# MCU.net
KiCad netlist of a schematic drawn in Altium Designer
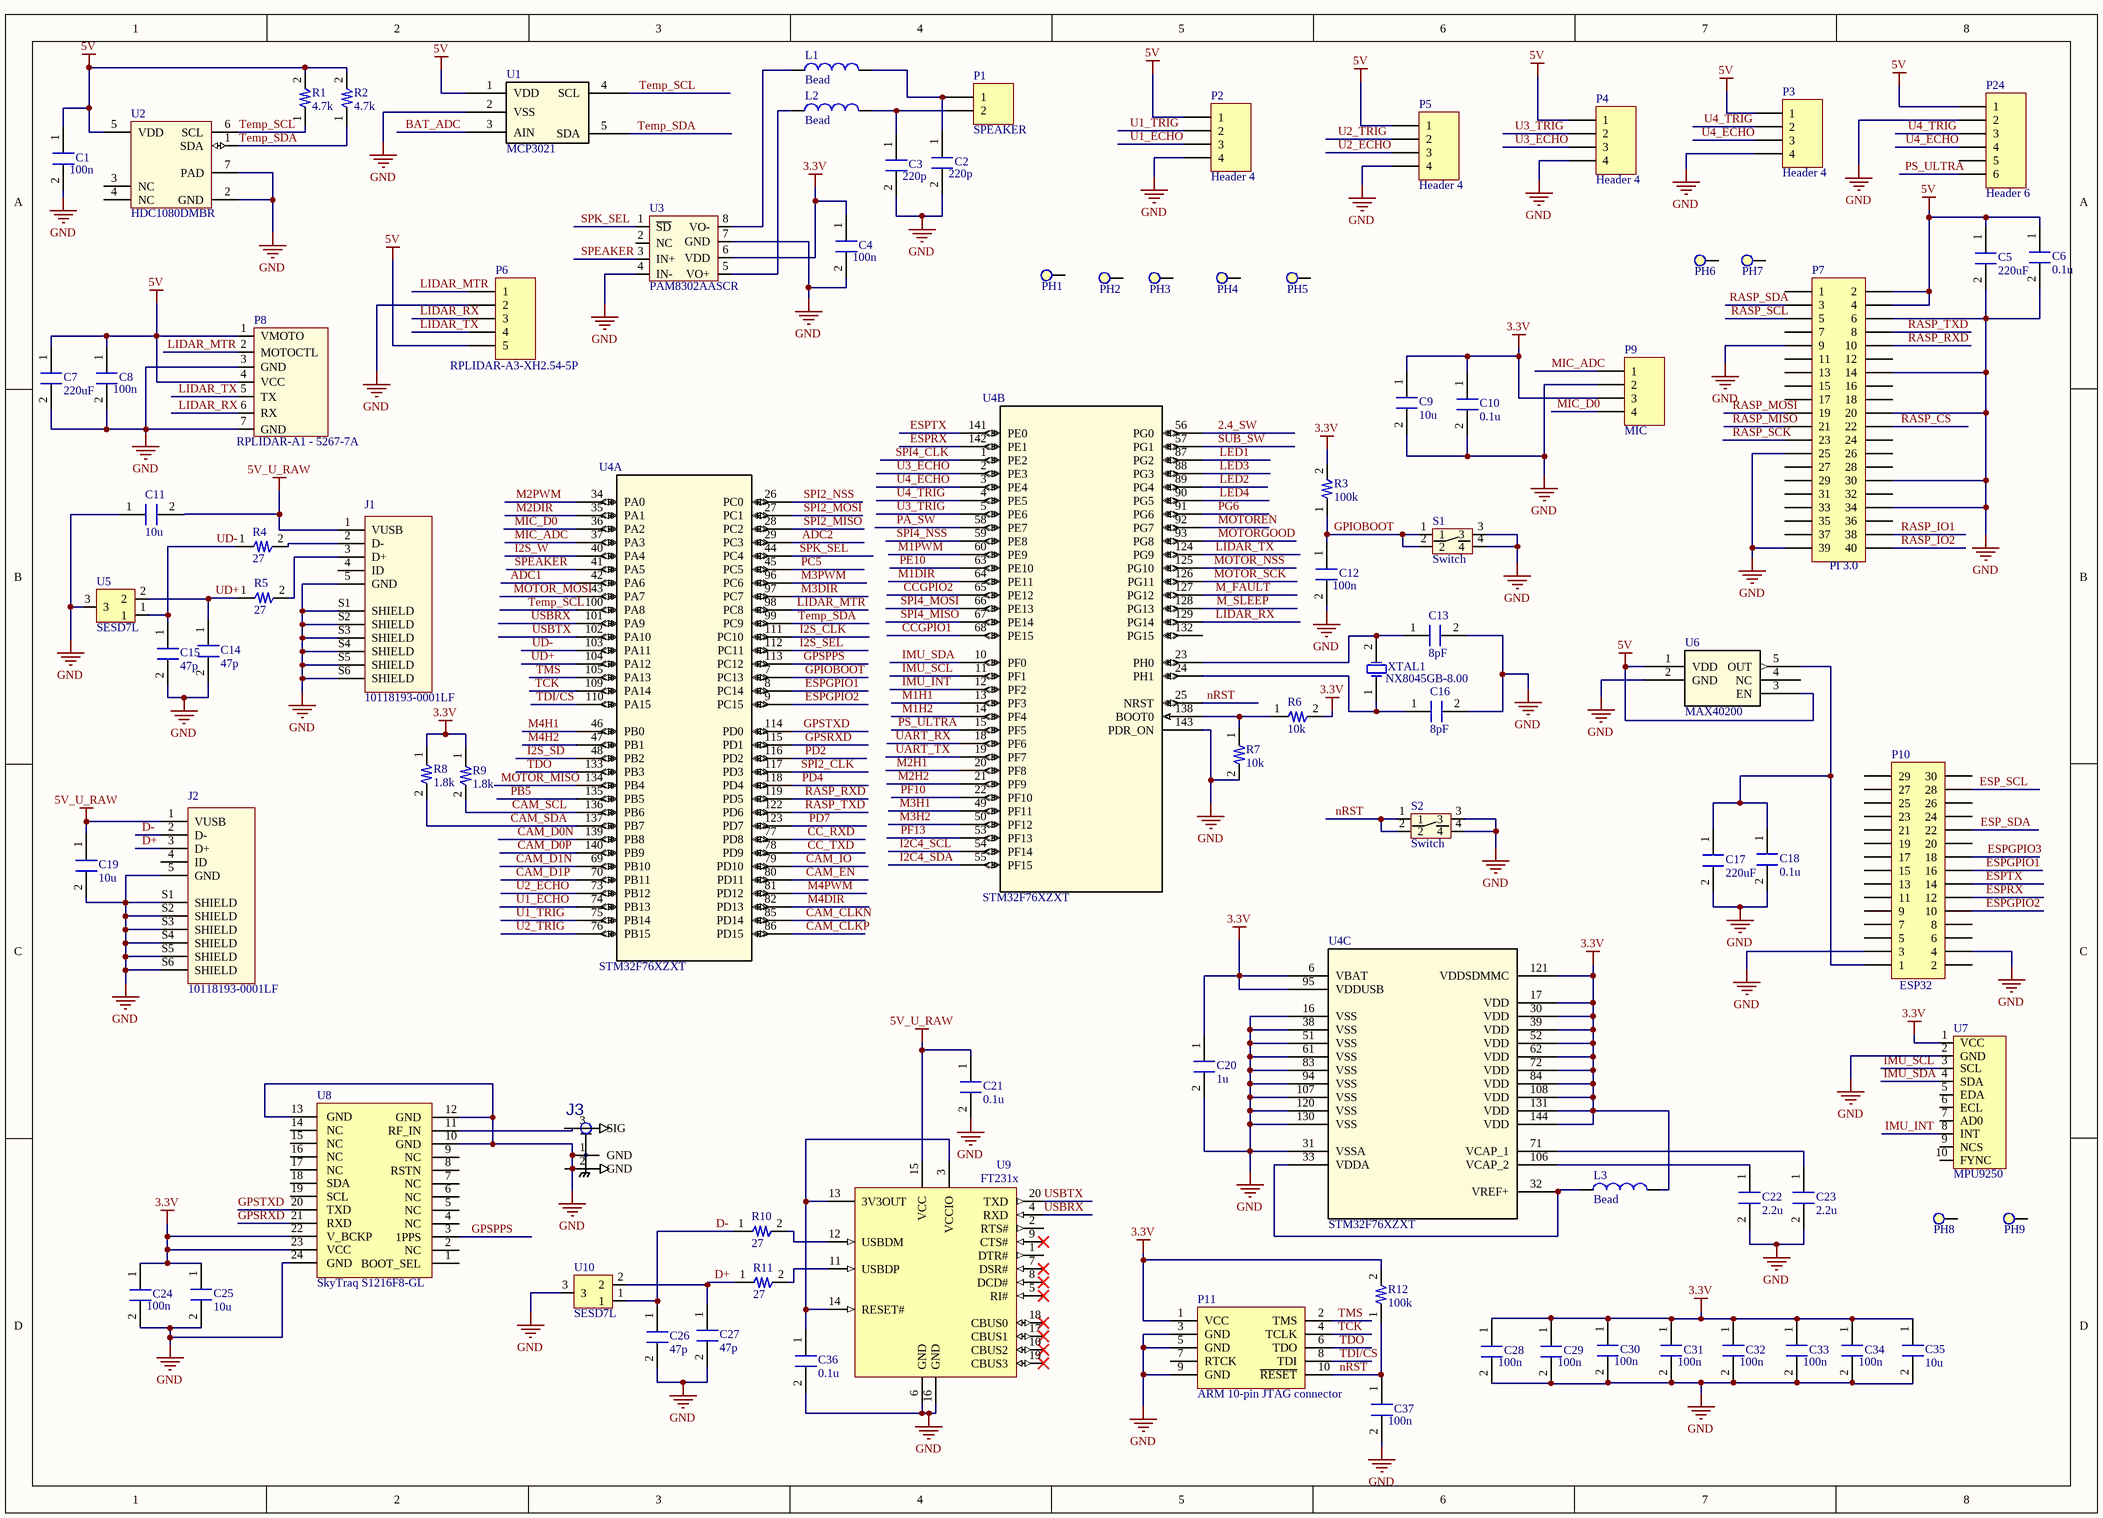
[diagram p0: MCU.SchDoc]

(export (version "E")
  (design (tool "Eeschema 10.0.6"))
  (components
    (comp (ref "C1")
      (value "100n")
      (footprint "Capacitor 0402")
      (fields (field (name "Comment") "Ceramic Capacitor"))
      (libsource (lib "Custom") (part "Ceramic Capacitor"))
    )
    (comp (ref "C2")
      (value "220p")
      (footprint "Capacitor 0402")
      (fields (field (name "Comment") "Ceramic Capacitor"))
      (libsource (lib "Custom") (part "Ceramic Capacitor"))
    )
    (comp (ref "C3")
      (value "220p")
      (footprint "Capacitor 0402")
      (fields (field (name "Comment") "Ceramic Capacitor"))
      (libsource (lib "Custom") (part "Ceramic Capacitor"))
    )
    (comp (ref "C4")
      (value "100n")
      (footprint "Capacitor 0402")
      (fields (field (name "Comment") "Ceramic Capacitor"))
      (libsource (lib "Custom") (part "Ceramic Capacitor"))
    )
    (comp (ref "C5")
      (value "220uF")
      (footprint "CAPAE250P680X1220_VERT")
      (fields (field (name "Comment") "Ceramic Capacitor"))
      (libsource (lib "Custom") (part "Ceramic Capacitor"))
    )
    (comp (ref "C6")
      (value "0.1u")
      (footprint "Capacitor 0402")
      (fields (field (name "Comment") "Ceramic Capacitor"))
      (libsource (lib "Custom") (part "Ceramic Capacitor"))
    )
    (comp (ref "C7")
      (value "220uF")
      (footprint "CAPAE250P680X1220_VERT")
      (fields (field (name "Comment") "Ceramic Capacitor"))
      (libsource (lib "Custom") (part "Ceramic Capacitor"))
    )
    (comp (ref "C8")
      (value "100n")
      (footprint "Capacitor 0402")
      (fields (field (name "Comment") "Ceramic Capacitor"))
      (libsource (lib "Custom") (part "Ceramic Capacitor"))
    )
    (comp (ref "C9")
      (value "10u")
      (footprint "Capacitor 0603")
      (fields (field (name "Comment") "Ceramic Capacitor"))
      (libsource (lib "Custom") (part "Ceramic Capacitor"))
    )
    (comp (ref "C10")
      (value "0.1u")
      (footprint "Capacitor 0402")
      (fields (field (name "Comment") "Ceramic Capacitor"))
      (libsource (lib "Custom") (part "Ceramic Capacitor"))
    )
    (comp (ref "C11")
      (value "10u")
      (footprint "Capacitor 0603")
      (fields (field (name "Comment") "Ceramic Capacitor"))
      (libsource (lib "Custom") (part "Ceramic Capacitor"))
    )
    (comp (ref "C12")
      (value "100n")
      (footprint "Capacitor 0402")
      (fields (field (name "Comment") "Ceramic Capacitor"))
      (libsource (lib "Custom") (part "Ceramic Capacitor"))
    )
    (comp (ref "C13")
      (value "8pF")
      (footprint "Capacitor 0402")
      (fields (field (name "Comment") "Ceramic Capacitor"))
      (libsource (lib "Custom") (part "Ceramic Capacitor"))
    )
    (comp (ref "C14")
      (value "47p")
      (footprint "Capacitor 0402")
      (fields (field (name "Comment") "Ceramic Capacitor"))
      (libsource (lib "Custom") (part "Ceramic Capacitor"))
    )
    (comp (ref "C15")
      (value "47p")
      (footprint "Capacitor 0402")
      (fields (field (name "Comment") "Ceramic Capacitor"))
      (libsource (lib "Custom") (part "Ceramic Capacitor"))
    )
    (comp (ref "C16")
      (value "8pF")
      (footprint "Capacitor 0402")
      (fields (field (name "Comment") "Ceramic Capacitor"))
      (libsource (lib "Custom") (part "Ceramic Capacitor"))
    )
    (comp (ref "C17")
      (value "220uF")
      (footprint "CAPAE250P680X1220_VERT")
      (fields (field (name "Comment") "Ceramic Capacitor"))
      (libsource (lib "Custom") (part "Ceramic Capacitor"))
    )
    (comp (ref "C18")
      (value "0.1u")
      (footprint "Capacitor 0402")
      (fields (field (name "Comment") "Ceramic Capacitor"))
      (libsource (lib "Custom") (part "Ceramic Capacitor"))
    )
    (comp (ref "C19")
      (value "10u")
      (footprint "Capacitor 0603")
      (fields (field (name "Comment") "Ceramic Capacitor"))
      (libsource (lib "Custom") (part "Ceramic Capacitor"))
    )
    (comp (ref "C20")
      (value "1u")
      (footprint "Capacitor 0402")
      (fields (field (name "Comment") "Ceramic Capacitor"))
      (libsource (lib "Custom") (part "Ceramic Capacitor"))
    )
    (comp (ref "C21")
      (value "0.1u")
      (footprint "Capacitor 0402")
      (fields (field (name "Comment") "Ceramic Capacitor"))
      (libsource (lib "Custom") (part "Ceramic Capacitor"))
    )
    (comp (ref "C22")
      (value "2.2u")
      (footprint "Capacitor 0402")
      (fields (field (name "Comment") "Ceramic Capacitor"))
      (libsource (lib "Custom") (part "Ceramic Capacitor"))
    )
    (comp (ref "C23")
      (value "2.2u")
      (footprint "Capacitor 0402")
      (fields (field (name "Comment") "Ceramic Capacitor"))
      (libsource (lib "Custom") (part "Ceramic Capacitor"))
    )
    (comp (ref "C24")
      (value "100n")
      (footprint "Capacitor 0402")
      (fields (field (name "Comment") "Ceramic Capacitor"))
      (libsource (lib "Custom") (part "Ceramic Capacitor"))
    )
    (comp (ref "C25")
      (value "10u")
      (footprint "Capacitor 0603")
      (fields (field (name "Comment") "Ceramic Capacitor"))
      (libsource (lib "Custom") (part "Ceramic Capacitor"))
    )
    (comp (ref "C26")
      (value "47p")
      (footprint "Capacitor 0402")
      (fields (field (name "Comment") "Ceramic Capacitor"))
      (libsource (lib "Custom") (part "Ceramic Capacitor"))
    )
    (comp (ref "C27")
      (value "47p")
      (footprint "Capacitor 0402")
      (fields (field (name "Comment") "Ceramic Capacitor"))
      (libsource (lib "Custom") (part "Ceramic Capacitor"))
    )
    (comp (ref "C28")
      (value "100n")
      (footprint "Capacitor 0402")
      (fields (field (name "Comment") "Ceramic Capacitor"))
      (libsource (lib "Custom") (part "Ceramic Capacitor"))
    )
    (comp (ref "C29")
      (value "100n")
      (footprint "Capacitor 0402")
      (fields (field (name "Comment") "Ceramic Capacitor"))
      (libsource (lib "Custom") (part "Ceramic Capacitor"))
    )
    (comp (ref "C30")
      (value "100n")
      (footprint "Capacitor 0402")
      (fields (field (name "Comment") "Ceramic Capacitor"))
      (libsource (lib "Custom") (part "Ceramic Capacitor"))
    )
    (comp (ref "C31")
      (value "100n")
      (footprint "Capacitor 0402")
      (fields (field (name "Comment") "Ceramic Capacitor"))
      (libsource (lib "Custom") (part "Ceramic Capacitor"))
    )
    (comp (ref "C32")
      (value "100n")
      (footprint "Capacitor 0402")
      (fields (field (name "Comment") "Ceramic Capacitor"))
      (libsource (lib "Custom") (part "Ceramic Capacitor"))
    )
    (comp (ref "C33")
      (value "100n")
      (footprint "Capacitor 0402")
      (fields (field (name "Comment") "Ceramic Capacitor"))
      (libsource (lib "Custom") (part "Ceramic Capacitor"))
    )
    (comp (ref "C34")
      (value "100n")
      (footprint "Capacitor 0402")
      (fields (field (name "Comment") "Ceramic Capacitor"))
      (libsource (lib "Custom") (part "Ceramic Capacitor"))
    )
    (comp (ref "C35")
      (value "10u")
      (footprint "Capacitor 0603")
      (fields (field (name "Comment") "Ceramic Capacitor"))
      (libsource (lib "Custom") (part "Ceramic Capacitor"))
    )
    (comp (ref "C36")
      (value "0.1u")
      (footprint "Capacitor 0402")
      (fields (field (name "Comment") "Ceramic Capacitor"))
      (libsource (lib "Custom") (part "Ceramic Capacitor"))
    )
    (comp (ref "C37")
      (value "100n")
      (footprint "Capacitor 0402")
      (fields (field (name "Comment") "Ceramic Capacitor"))
      (libsource (lib "Custom") (part "Ceramic Capacitor"))
    )
    (comp (ref "J1")
      (value "10118193-0001LF")
      (footprint "FCI_10118193-0001LF_10118193-0001LF(Primary)")
      (description "USB mini")
      (libsource (lib "Custom") (part "USB mini 10118193-0001LF"))
    )
    (comp (ref "J2")
      (value "10118193-0001LF")
      (footprint "FCI_10118193-0001LF_10118193-0001LF(Primary)")
      (description "USB mini")
      (libsource (lib "Custom") (part "USB mini 10118193-0001LF"))
    )
    (comp (ref "J3")
      (value "U.FL-R-SMT(01)")
      (footprint "HRS_U.FL-R-SMT(01)")
      (description "U.FL Series 6 Ghz 50 Ohm Ultra-small SMT Coaxial Cable Receptacle")
      (fields (field (name "MF") "Hirose"))
      (libsource (lib "Custom") (part "U.FL-R-SMT(01)"))
    )
    (comp (ref "L1")
      (value "Bead")
      (footprint "Resistor 0603")
      (description "Inductor")
      (libsource (lib "Custom") (part "Inductor"))
    )
    (comp (ref "L2")
      (value "Bead")
      (footprint "Resistor 0603")
      (description "Inductor")
      (libsource (lib "Custom") (part "Inductor"))
    )
    (comp (ref "L3")
      (value "Bead")
      (footprint "Resistor 0603")
      (description "Inductor")
      (libsource (lib "Custom") (part "Inductor"))
    )
    (comp (ref "P1")
      (value "SPEAKER")
      (footprint "HDR1X2")
      (description "Header, 2-Pin")
      (fields (field (name "PUBLISHER") "Altium Limited"))
      (libsource (lib "Miscellaneous Connectors") (part "Header 2"))
    )
    (comp (ref "P2")
      (value "Header 4")
      (footprint "HDR1X4")
      (description "Header, 4-Pin")
      (fields (field (name "PUBLISHER") "Altium Limited"))
      (libsource (lib "Miscellaneous Connectors") (part "Header 4"))
    )
    (comp (ref "P3")
      (value "Header 4")
      (footprint "HDR1X4")
      (description "Header, 4-Pin")
      (fields (field (name "PUBLISHER") "Altium Limited"))
      (libsource (lib "Miscellaneous Connectors") (part "Header 4"))
    )
    (comp (ref "P4")
      (value "Header 4")
      (footprint "HDR1X4")
      (description "Header, 4-Pin")
      (fields (field (name "PUBLISHER") "Altium Limited"))
      (libsource (lib "Miscellaneous Connectors") (part "Header 4"))
    )
    (comp (ref "P5")
      (value "Header 4")
      (footprint "HDR1X4")
      (description "Header, 4-Pin")
      (fields (field (name "PUBLISHER") "Altium Limited"))
      (libsource (lib "Miscellaneous Connectors") (part "Header 4"))
    )
    (comp (ref "P6")
      (value "RPLIDAR-A3-XH2.54-5P")
      (footprint "HDR1X5")
      (description "Header, 5-Pin")
      (fields (field (name "PUBLISHER") "Altium Limited"))
      (libsource (lib "Miscellaneous Connectors") (part "Header 5"))
    )
    (comp (ref "P7")
      (value "PI 3.0")
      (footprint "HDR2X20")
      (description "Header, 20-Pin, Dual row")
      (fields (field (name "PUBLISHER") "Altium Limited"))
      (libsource (lib "Miscellaneous Connectors") (part "Header 20X2"))
    )
    (comp (ref "P8")
      (value "RPLIDAR-A1 - 5267-7A")
      (footprint "HDR1X7")
      (libsource (lib "Custom") (part "RPLIDAR A1"))
    )
    (comp (ref "P9")
      (value "MIC")
      (footprint "HDR1X4")
      (description "Header, 4-Pin")
      (fields (field (name "PUBLISHER") "Altium Limited"))
      (libsource (lib "Miscellaneous Connectors") (part "Header 4"))
    )
    (comp (ref "P10")
      (value "ESP32")
      (footprint "ESP32")
      (description "Header, 15-Pin, Dual row")
      (fields (field (name "PUBLISHER") "Altium Limited"))
      (libsource (lib "Miscellaneous Connectors") (part "Header 15X2"))
    )
    (comp (ref "P11")
      (value "ARM 10-pin JTAG connector")
      (footprint "MHDR2X5")
      (description "ARM JTAG/SWD connector")
      (libsource (lib "Custom") (part "ARM JTAG"))
    )
    (comp (ref "P24")
      (value "Header 6")
      (footprint "HDR1X6")
      (description "Header, 6-Pin")
      (fields (field (name "PUBLISHER") "Altium Limited"))
      (libsource (lib "Miscellaneous Connectors") (part "Header 6"))
    )
    (comp (ref "PH1")
      (value "Plated Hole")
      (footprint "PH-M3-A")
      (description "Plated hole for threaded rods")
      (fields (field (name "PUBLISHER") "N.F.Baltazar Santos - DelFFi"))
      (libsource (lib "Custom") (part "PH"))
    )
    (comp (ref "PH2")
      (value "Plated Hole")
      (footprint "PH-M3-A")
      (description "Plated hole for threaded rods")
      (fields (field (name "PUBLISHER") "N.F.Baltazar Santos - DelFFi"))
      (libsource (lib "Custom") (part "PH"))
    )
    (comp (ref "PH3")
      (value "Plated Hole")
      (footprint "PH-M3-A")
      (description "Plated hole for threaded rods")
      (fields (field (name "PUBLISHER") "N.F.Baltazar Santos - DelFFi"))
      (libsource (lib "Custom") (part "PH"))
    )
    (comp (ref "PH4")
      (value "Plated Hole")
      (footprint "PH-M3-A")
      (description "Plated hole for threaded rods")
      (fields (field (name "PUBLISHER") "N.F.Baltazar Santos - DelFFi"))
      (libsource (lib "Custom") (part "PH"))
    )
    (comp (ref "PH5")
      (value "Plated Hole")
      (footprint "PH-M3-A")
      (description "Plated hole for threaded rods")
      (fields (field (name "PUBLISHER") "N.F.Baltazar Santos - DelFFi"))
      (libsource (lib "Custom") (part "PH"))
    )
    (comp (ref "PH6")
      (value "Plated Hole")
      (footprint "PH-M2-A")
      (description "Plated hole for threaded rods")
      (fields (field (name "PUBLISHER") "N.F.Baltazar Santos - DelFFi"))
      (libsource (lib "Custom") (part "PH"))
    )
    (comp (ref "PH7")
      (value "Plated Hole")
      (footprint "PH-M2-A")
      (description "Plated hole for threaded rods")
      (fields (field (name "PUBLISHER") "N.F.Baltazar Santos - DelFFi"))
      (libsource (lib "Custom") (part "PH"))
    )
    (comp (ref "PH8")
      (value "Plated Hole")
      (footprint "PH-M3-A")
      (description "Plated hole for threaded rods")
      (fields (field (name "PUBLISHER") "N.F.Baltazar Santos - DelFFi"))
      (libsource (lib "Custom") (part "PH"))
    )
    (comp (ref "PH9")
      (value "Plated Hole")
      (footprint "PH-M3-A")
      (description "Plated hole for threaded rods")
      (fields (field (name "PUBLISHER") "N.F.Baltazar Santos - DelFFi"))
      (libsource (lib "Custom") (part "PH"))
    )
    (comp (ref "R1")
      (value "4.7k")
      (footprint "Resistor 0402")
      (description "General Purpose Resistor")
      (fields (field (name "Comment") "Resistor"))
      (libsource (lib "Custom") (part "Resistor"))
    )
    (comp (ref "R2")
      (value "4.7k")
      (footprint "Resistor 0402")
      (description "General Purpose Resistor")
      (fields (field (name "Comment") "Resistor"))
      (libsource (lib "Custom") (part "Resistor"))
    )
    (comp (ref "R3")
      (value "100k")
      (footprint "Resistor 0402")
      (description "General Purpose Resistor")
      (fields (field (name "Comment") "Resistor"))
      (libsource (lib "Custom") (part "Resistor"))
    )
    (comp (ref "R4")
      (value "27")
      (footprint "Resistor 0402")
      (description "General Purpose Resistor")
      (fields (field (name "Comment") "Resistor"))
      (libsource (lib "Custom") (part "Resistor"))
    )
    (comp (ref "R5")
      (value "27")
      (footprint "Resistor 0402")
      (description "General Purpose Resistor")
      (fields (field (name "Comment") "Resistor"))
      (libsource (lib "Custom") (part "Resistor"))
    )
    (comp (ref "R6")
      (value "10k")
      (footprint "Resistor 0402")
      (description "General Purpose Resistor")
      (fields (field (name "Comment") "Resistor"))
      (libsource (lib "Custom") (part "Resistor"))
    )
    (comp (ref "R7")
      (value "10k")
      (footprint "Resistor 0402")
      (description "General Purpose Resistor")
      (fields (field (name "Comment") "Resistor"))
      (libsource (lib "Custom") (part "Resistor"))
    )
    (comp (ref "R8")
      (value "1.8k")
      (footprint "Resistor 0402")
      (description "General Purpose Resistor")
      (fields (field (name "Comment") "Resistor"))
      (libsource (lib "Custom") (part "Resistor"))
    )
    (comp (ref "R9")
      (value "1.8k")
      (footprint "Resistor 0402")
      (description "General Purpose Resistor")
      (fields (field (name "Comment") "Resistor"))
      (libsource (lib "Custom") (part "Resistor"))
    )
    (comp (ref "R10")
      (value "27")
      (footprint "Resistor 0402")
      (description "General Purpose Resistor")
      (fields (field (name "Comment") "Resistor"))
      (libsource (lib "Custom") (part "Resistor"))
    )
    (comp (ref "R11")
      (value "27")
      (footprint "Resistor 0402")
      (description "General Purpose Resistor")
      (fields (field (name "Comment") "Resistor"))
      (libsource (lib "Custom") (part "Resistor"))
    )
    (comp (ref "R12")
      (value "100k")
      (footprint "Resistor 0402")
      (description "General Purpose Resistor")
      (fields (field (name "Comment") "Resistor"))
      (libsource (lib "Custom") (part "Resistor"))
    )
    (comp (ref "S1") (value "Switch") (footprint "Switch") (libsource (lib "Custom") (part "Switch")))
    (comp (ref "S2") (value "Switch") (footprint "Switch") (libsource (lib "Custom") (part "Switch")))
    (comp (ref "U1")
      (value "MCP3021")
      (footprint "SOT23-5N")
      (description "ADC")
      (libsource (lib "Custom") (part "MCP3021"))
    )
    (comp (ref "U2")
      (value "HDC1080DMBR")
      (footprint "DMB0006A")
      (description "No Description Available")
      (libsource (lib "Custom") (part "HDC1080DMBR"))
    )
    (comp (ref "U3")
      (value "PAM8302AASCR")
      (footprint "MSOP-MS8_N")
      (description "Speaker amplifier")
      (libsource (lib "Custom") (part "PAM8302AASCR"))
    )
    (comp (ref "U4")
      (value "STM32F76XZXT")
      (footprint "LQFP-144_20X20mm")
      (description "Imported")
      (fields
        (field (name "MANUFACTURER_PART_NUMBER") "stm32f76xzxt")
        (field (name "COPYRIGHT") "Copyright (C) 2016 Accelerated Designs. All rights reserved")
      )
      (libsource (lib "Custom") (part "STM32F76XZXT"))
    )
    (comp (ref "U5")
      (value "SESD7L")
      (footprint "SOT-723")
      (description "TVS Diode - USB")
      (libsource (lib "Custom") (part "SESD7L"))
    )
    (comp (ref "U6")
      (value "MAX40200")
      (footprint "21-0057F")
      (description "No Description Available")
      (libsource (lib "Custom") (part "MAX40200"))
    )
    (comp (ref "U7") (value "MPU9250") (footprint "HDR1X10") (libsource (lib "Custom") (part "MPU9250")))
    (comp (ref "U8")
      (value "SkyTraq S1216F8-GL")
      (footprint "SkyTraq S1216F8-GL")
      (description "Skytraq S1216F8-GL GPS chip")
      (libsource (lib "Custom") (part "SkyTraq S1216F8-GL"))
    )
    (comp (ref "U9") (value "FT231x") (footprint "SSOP-20_N") (libsource (lib "Custom") (part "FT231x")))
    (comp (ref "U10")
      (value "SESD7L")
      (footprint "SOT-723")
      (description "TVS Diode - USB")
      (libsource (lib "Custom") (part "SESD7L"))
    )
    (comp (ref "XTAL1")
      (value "NX8045GB-8.00")
      (footprint "NX8045G 8MHz Crystal")
      (description "Surface Mount Quartz Crystal")
      (libsource (lib "Custom") (part "NDK NX8045G 8MHz"))
    )
  )
  (nets
    (net (code "1") (name "/2.4_SW") (class "Default")
      (node (ref "U4") (pin "56") (pinfunction "PG0_56") (pintype "bidirectional"))
    )
    (net (code "2") (name "/ADC1") (class "Default")
      (node (ref "U4") (pin "42") (pinfunction "PA6_42") (pintype "bidirectional"))
    )
    (net (code "3") (name "/ADC2") (class "Default")
      (node (ref "U4") (pin "29") (pinfunction "PC3_29") (pintype "bidirectional"))
    )
    (net (code "4") (name "/BAT_ADC") (class "Default")
      (node (ref "U1") (pin "3") (pinfunction "AIN_3") (pintype "passive"))
    )
    (net (code "5") (name "/CAM_CLKN") (class "Default")
      (node (ref "U4") (pin "85") (pinfunction "PD14_85") (pintype "bidirectional"))
    )
    (net (code "6") (name "/CAM_CLKP") (class "Default")
      (node (ref "U4") (pin "86") (pinfunction "PD15_86") (pintype "bidirectional"))
    )
    (net (code "7") (name "/CAM_D0N") (class "Default")
      (node (ref "U4") (pin "139") (pinfunction "PB8_139") (pintype "bidirectional"))
    )
    (net (code "8") (name "/CAM_D0P") (class "Default")
      (node (ref "U4") (pin "140") (pinfunction "PB9_140") (pintype "bidirectional"))
    )
    (net (code "9") (name "/CAM_D1N") (class "Default")
      (node (ref "U4") (pin "69") (pinfunction "PB10_69") (pintype "bidirectional"))
    )
    (net (code "10") (name "/CAM_D1P") (class "Default")
      (node (ref "U4") (pin "70") (pinfunction "PB11_70") (pintype "bidirectional"))
    )
    (net (code "11") (name "/CAM_EN") (class "Default")
      (node (ref "U4") (pin "80") (pinfunction "PD11_80") (pintype "bidirectional"))
    )
    (net (code "12") (name "/CAM_IO") (class "Default")
      (node (ref "U4") (pin "79") (pinfunction "PD10_79") (pintype "bidirectional"))
    )
    (net (code "13") (name "/CAM_SCL") (class "Default")
      (node (ref "R9") (pin "2") (pinfunction "2_2") (pintype "passive"))
      (node (ref "U4") (pin "136") (pinfunction "PB6_136") (pintype "bidirectional"))
    )
    (net (code "14") (name "/CAM_SDA") (class "Default")
      (node (ref "R8") (pin "2") (pinfunction "2_2") (pintype "passive"))
      (node (ref "U4") (pin "137") (pinfunction "PB7_137") (pintype "bidirectional"))
    )
    (net (code "15") (name "/CCGPIO1") (class "Default")
      (node (ref "U4") (pin "68") (pinfunction "PE15_68") (pintype "bidirectional"))
    )
    (net (code "16") (name "/CCGPIO2") (class "Default")
      (node (ref "U4") (pin "65") (pinfunction "PE12_65") (pintype "bidirectional"))
    )
    (net (code "17") (name "/CC_RXD") (class "Default")
      (node (ref "U4") (pin "77") (pinfunction "PD8_77") (pintype "bidirectional"))
    )
    (net (code "18") (name "/CC_TXD") (class "Default")
      (node (ref "U4") (pin "78") (pinfunction "PD9_78") (pintype "bidirectional"))
    )
    (net (code "19") (name "/D+") (class "Default")
      (node (ref "C27") (pin "1") (pinfunction "1_1") (pintype "passive"))
      (node (ref "J2") (pin "3") (pinfunction "D+_3") (pintype "passive"))
      (node (ref "R11") (pin "1") (pinfunction "1_1") (pintype "passive"))
      (node (ref "U10") (pin "2") (pinfunction "2_2") (pintype "passive"))
    )
    (net (code "20") (name "/D-") (class "Default")
      (node (ref "C26") (pin "1") (pinfunction "1_1") (pintype "passive"))
      (node (ref "J2") (pin "2") (pinfunction "D-_2") (pintype "passive"))
      (node (ref "R10") (pin "1") (pinfunction "1_1") (pintype "passive"))
      (node (ref "U10") (pin "1") (pinfunction "1_1") (pintype "passive"))
    )
    (net (code "21") (name "/ESPGPIO1") (class "Default")
      (node (ref "P10") (pin "16") (pinfunction "16_16") (pintype "passive"))
      (node (ref "U4") (pin "8") (pinfunction "PC14_8") (pintype "bidirectional"))
    )
    (net (code "22") (name "/ESPGPIO2") (class "Default")
      (node (ref "P10") (pin "10") (pinfunction "10_10") (pintype "passive"))
      (node (ref "U4") (pin "9") (pinfunction "PC15_9") (pintype "bidirectional"))
    )
    (net (code "23") (name "/ESPGPIO3") (class "Default")
      (node (ref "P10") (pin "18") (pinfunction "18_18") (pintype "passive"))
    )
    (net (code "24") (name "/ESPRX") (class "Default")
      (node (ref "P10") (pin "12") (pinfunction "12_12") (pintype "passive"))
      (node (ref "U4") (pin "142") (pinfunction "PE1_142") (pintype "bidirectional"))
    )
    (net (code "25") (name "/ESPTX") (class "Default")
      (node (ref "P10") (pin "14") (pinfunction "14_14") (pintype "passive"))
      (node (ref "U4") (pin "141") (pinfunction "PE0_141") (pintype "bidirectional"))
    )
    (net (code "26") (name "/ESP_SCL") (class "Default")
      (node (ref "P10") (pin "28") (pinfunction "28_28") (pintype "passive"))
    )
    (net (code "27") (name "/ESP_SDA") (class "Default")
      (node (ref "P10") (pin "22") (pinfunction "22_22") (pintype "passive"))
    )
    (net (code "28") (name "/GPIOBOOT") (class "Default")
      (node (ref "C12") (pin "1") (pinfunction "1_1") (pintype "passive"))
      (node (ref "R3") (pin "1") (pinfunction "1_1") (pintype "passive"))
      (node (ref "S1") (pin "1") (pinfunction "1_1") (pintype "passive"))
      (node (ref "S1") (pin "2") (pinfunction "2_2") (pintype "passive"))
      (node (ref "U4") (pin "7") (pinfunction "PC13_7") (pintype "bidirectional"))
    )
    (net (code "29") (name "/GPSPPS") (class "Default")
      (node (ref "U4") (pin "113") (pinfunction "PC12_113") (pintype "bidirectional"))
      (node (ref "U8") (pin "3") (pinfunction "1PPS_3") (pintype "passive"))
    )
    (net (code "30") (name "/GPSRXD") (class "Default")
      (node (ref "U4") (pin "115") (pinfunction "PD1_115") (pintype "bidirectional"))
      (node (ref "U8") (pin "21") (pinfunction "RXD_21") (pintype "passive"))
    )
    (net (code "31") (name "/GPSTXD") (class "Default")
      (node (ref "U4") (pin "114") (pinfunction "PD0_114") (pintype "bidirectional"))
      (node (ref "U8") (pin "20") (pinfunction "TXD_20") (pintype "passive"))
    )
    (net (code "32") (name "/I2C4_SCL") (class "Default")
      (node (ref "U4") (pin "54") (pinfunction "PF14_54") (pintype "bidirectional"))
    )
    (net (code "33") (name "/I2C4_SDA") (class "Default")
      (node (ref "U4") (pin "55") (pinfunction "PF15_55") (pintype "bidirectional"))
    )
    (net (code "34") (name "/I2S_CLK") (class "Default")
      (node (ref "U4") (pin "111") (pinfunction "PC10_111") (pintype "bidirectional"))
    )
    (net (code "35") (name "/I2S_SD") (class "Default")
      (node (ref "U4") (pin "48") (pinfunction "PB2_48") (pintype "bidirectional"))
    )
    (net (code "36") (name "/I2S_SEL") (class "Default")
      (node (ref "U4") (pin "112") (pinfunction "PC11_112") (pintype "bidirectional"))
    )
    (net (code "37") (name "/I2S_W") (class "Default")
      (node (ref "U4") (pin "40") (pinfunction "PA4_40") (pintype "bidirectional"))
    )
    (net (code "38") (name "/IMU_INT") (class "Default")
      (node (ref "U4") (pin "12") (pinfunction "PF2_12") (pintype "bidirectional"))
      (node (ref "U7") (pin "8") (pinfunction "INT_8") (pintype "passive"))
    )
    (net (code "39") (name "/IMU_SCL") (class "Default")
      (node (ref "U4") (pin "11") (pinfunction "PF1_11") (pintype "bidirectional"))
      (node (ref "U7") (pin "3") (pinfunction "SCL_3") (pintype "passive"))
    )
    (net (code "40") (name "/IMU_SDA") (class "Default")
      (node (ref "U4") (pin "10") (pinfunction "PF0_10") (pintype "bidirectional"))
      (node (ref "U7") (pin "4") (pinfunction "SDA_4") (pintype "passive"))
    )
    (net (code "41") (name "/LED1") (class "Default")
      (node (ref "U4") (pin "87") (pinfunction "PG2_87") (pintype "bidirectional"))
    )
    (net (code "42") (name "/LED2") (class "Default")
      (node (ref "U4") (pin "89") (pinfunction "PG4_89") (pintype "bidirectional"))
    )
    (net (code "43") (name "/LED3") (class "Default")
      (node (ref "U4") (pin "88") (pinfunction "PG3_88") (pintype "bidirectional"))
    )
    (net (code "44") (name "/LED4") (class "Default")
      (node (ref "U4") (pin "90") (pinfunction "PG5_90") (pintype "bidirectional"))
    )
    (net (code "45") (name "/LIDAR_MTR") (class "Default")
      (node (ref "P6") (pin "1") (pinfunction "1_1") (pintype "passive"))
      (node (ref "P8") (pin "2") (pinfunction "MOTOCTL_2") (pintype "passive"))
      (node (ref "U4") (pin "98") (pinfunction "PC8_98") (pintype "bidirectional"))
    )
    (net (code "46") (name "/LIDAR_RX") (class "Default")
      (node (ref "P6") (pin "3") (pinfunction "3_3") (pintype "passive"))
      (node (ref "P8") (pin "6") (pinfunction "RX_6") (pintype "passive"))
      (node (ref "U4") (pin "129") (pinfunction "PG14_129") (pintype "bidirectional"))
    )
    (net (code "47") (name "/LIDAR_TX") (class "Default")
      (node (ref "P6") (pin "4") (pinfunction "4_4") (pintype "passive"))
      (node (ref "P8") (pin "5") (pinfunction "TX_5") (pintype "passive"))
      (node (ref "U4") (pin "124") (pinfunction "PG9_124") (pintype "bidirectional"))
    )
    (net (code "48") (name "/M1DIR") (class "Default")
      (node (ref "U4") (pin "64") (pinfunction "PE11_64") (pintype "bidirectional"))
    )
    (net (code "49") (name "/M1H1") (class "Default")
      (node (ref "U4") (pin "13") (pinfunction "PF3_13") (pintype "bidirectional"))
    )
    (net (code "50") (name "/M1H2") (class "Default")
      (node (ref "U4") (pin "14") (pinfunction "PF4_14") (pintype "bidirectional"))
    )
    (net (code "51") (name "/M1PWM") (class "Default")
      (node (ref "U4") (pin "60") (pinfunction "PE9_60") (pintype "bidirectional"))
    )
    (net (code "52") (name "/M2DIR") (class "Default")
      (node (ref "U4") (pin "35") (pinfunction "PA1_35") (pintype "bidirectional"))
    )
    (net (code "53") (name "/M2H1") (class "Default")
      (node (ref "U4") (pin "20") (pinfunction "PF8_20") (pintype "bidirectional"))
    )
    (net (code "54") (name "/M2H2") (class "Default")
      (node (ref "U4") (pin "21") (pinfunction "PF9_21") (pintype "bidirectional"))
    )
    (net (code "55") (name "/M2PWM") (class "Default")
      (node (ref "U4") (pin "34") (pinfunction "PA0_34") (pintype "bidirectional"))
    )
    (net (code "56") (name "/M3DIR") (class "Default")
      (node (ref "U4") (pin "97") (pinfunction "PC7_97") (pintype "bidirectional"))
    )
    (net (code "57") (name "/M3H1") (class "Default")
      (node (ref "U4") (pin "49") (pinfunction "PF11_49") (pintype "bidirectional"))
    )
    (net (code "58") (name "/M3H2") (class "Default")
      (node (ref "U4") (pin "50") (pinfunction "PF12_50") (pintype "bidirectional"))
    )
    (net (code "59") (name "/M3PWM") (class "Default")
      (node (ref "U4") (pin "96") (pinfunction "PC6_96") (pintype "bidirectional"))
    )
    (net (code "60") (name "/M4DIR") (class "Default")
      (node (ref "U4") (pin "82") (pinfunction "PD13_82") (pintype "bidirectional"))
    )
    (net (code "61") (name "/M4H1") (class "Default")
      (node (ref "U4") (pin "46") (pinfunction "PB0_46") (pintype "bidirectional"))
    )
    (net (code "62") (name "/M4H2") (class "Default")
      (node (ref "U4") (pin "47") (pinfunction "PB1_47") (pintype "bidirectional"))
    )
    (net (code "63") (name "/M4PWM") (class "Default")
      (node (ref "U4") (pin "81") (pinfunction "PD12_81") (pintype "bidirectional"))
    )
    (net (code "64") (name "/MIC_ADC") (class "Default")
      (node (ref "P9") (pin "1") (pinfunction "1_1") (pintype "passive"))
      (node (ref "U4") (pin "37") (pinfunction "PA3_37") (pintype "bidirectional"))
    )
    (net (code "65") (name "/MIC_D0") (class "Default")
      (node (ref "P9") (pin "4") (pinfunction "4_4") (pintype "passive"))
      (node (ref "U4") (pin "36") (pinfunction "PA2_36") (pintype "bidirectional"))
    )
    (net (code "66") (name "/MOTOREN") (class "Default")
      (node (ref "U4") (pin "92") (pinfunction "PG7_92") (pintype "bidirectional"))
    )
    (net (code "67") (name "/MOTORGOOD") (class "Default")
      (node (ref "U4") (pin "93") (pinfunction "PG8_93") (pintype "bidirectional"))
    )
    (net (code "68") (name "/MOTOR_MISO") (class "Default")
      (node (ref "U4") (pin "134") (pinfunction "PB4_134") (pintype "bidirectional"))
    )
    (net (code "69") (name "/MOTOR_MOSI") (class "Default")
      (node (ref "U4") (pin "43") (pinfunction "PA7_43") (pintype "bidirectional"))
    )
    (net (code "70") (name "/MOTOR_NSS") (class "Default")
      (node (ref "U4") (pin "125") (pinfunction "PG10_125") (pintype "bidirectional"))
    )
    (net (code "71") (name "/MOTOR_SCK") (class "Default")
      (node (ref "U4") (pin "126") (pinfunction "PG11_126") (pintype "bidirectional"))
    )
    (net (code "72") (name "/M_FAULT") (class "Default")
      (node (ref "U4") (pin "127") (pinfunction "PG12_127") (pintype "bidirectional"))
    )
    (net (code "73") (name "/M_SLEEP") (class "Default")
      (node (ref "U4") (pin "128") (pinfunction "PG13_128") (pintype "bidirectional"))
    )
    (net (code "74") (name "/PA_SW") (class "Default")
      (node (ref "U4") (pin "58") (pinfunction "PE7_58") (pintype "bidirectional"))
    )
    (net (code "75") (name "/PB5") (class "Default")
      (node (ref "U4") (pin "135") (pinfunction "PB5_135") (pintype "bidirectional"))
    )
    (net (code "76") (name "/PC5") (class "Default")
      (node (ref "U4") (pin "45") (pinfunction "PC5_45") (pintype "bidirectional"))
    )
    (net (code "77") (name "/PD2") (class "Default")
      (node (ref "U4") (pin "116") (pinfunction "PD2_116") (pintype "bidirectional"))
    )
    (net (code "78") (name "/PD4") (class "Default")
      (node (ref "U4") (pin "118") (pinfunction "PD4_118") (pintype "bidirectional"))
    )
    (net (code "79") (name "/PD7") (class "Default")
      (node (ref "U4") (pin "123") (pinfunction "PD7_123") (pintype "bidirectional"))
    )
    (net (code "80") (name "/PE10") (class "Default")
      (node (ref "U4") (pin "63") (pinfunction "PE10_63") (pintype "bidirectional"))
    )
    (net (code "81") (name "/PF10") (class "Default")
      (node (ref "U4") (pin "22") (pinfunction "PF10_22") (pintype "bidirectional"))
    )
    (net (code "82") (name "/PF13") (class "Default")
      (node (ref "U4") (pin "53") (pinfunction "PF13_53") (pintype "bidirectional"))
    )
    (net (code "83") (name "/PG6") (class "Default")
      (node (ref "U4") (pin "91") (pinfunction "PG6_91") (pintype "bidirectional"))
    )
    (net (code "84") (name "/PS_ULTRA") (class "Default")
      (node (ref "P24") (pin "6") (pinfunction "6_6") (pintype "passive"))
      (node (ref "U4") (pin "15") (pinfunction "PF5_15") (pintype "bidirectional"))
    )
    (net (code "85") (name "/RASP_CS") (class "Default")
      (node (ref "P7") (pin "22") (pinfunction "22_22") (pintype "passive"))
    )
    (net (code "86") (name "/RASP_IO1") (class "Default")
      (node (ref "P7") (pin "38") (pinfunction "38_38") (pintype "passive"))
    )
    (net (code "87") (name "/RASP_IO2") (class "Default")
      (node (ref "P7") (pin "40") (pinfunction "40_40") (pintype "passive"))
    )
    (net (code "88") (name "/RASP_MISO") (class "Default")
      (node (ref "P7") (pin "21") (pinfunction "21_21") (pintype "passive"))
    )
    (net (code "89") (name "/RASP_MOSI") (class "Default")
      (node (ref "P7") (pin "19") (pinfunction "19_19") (pintype "passive"))
    )
    (net (code "90") (name "/RASP_RXD") (class "Default")
      (node (ref "P7") (pin "10") (pinfunction "10_10") (pintype "passive"))
      (node (ref "U4") (pin "119") (pinfunction "PD5_119") (pintype "bidirectional"))
    )
    (net (code "91") (name "/RASP_SCK") (class "Default")
      (node (ref "P7") (pin "23") (pinfunction "23_23") (pintype "passive"))
    )
    (net (code "92") (name "/RASP_SCL") (class "Default")
      (node (ref "P7") (pin "5") (pinfunction "5_5") (pintype "passive"))
    )
    (net (code "93") (name "/RASP_SDA") (class "Default")
      (node (ref "P7") (pin "3") (pinfunction "3_3") (pintype "passive"))
    )
    (net (code "94") (name "/RASP_TXD") (class "Default")
      (node (ref "P7") (pin "8") (pinfunction "8_8") (pintype "passive"))
      (node (ref "U4") (pin "122") (pinfunction "PD6_122") (pintype "bidirectional"))
    )
    (net (code "95") (name "/SPEAKER") (class "Default")
      (node (ref "U3") (pin "3") (pinfunction "IN+_3") (pintype "passive"))
      (node (ref "U4") (pin "41") (pinfunction "PA5_41") (pintype "bidirectional"))
    )
    (net (code "96") (name "/SPI2_CLK") (class "Default")
      (node (ref "U4") (pin "117") (pinfunction "PD3_117") (pintype "bidirectional"))
    )
    (net (code "97") (name "/SPI2_MISO") (class "Default")
      (node (ref "U4") (pin "28") (pinfunction "PC2_28") (pintype "bidirectional"))
    )
    (net (code "98") (name "/SPI2_MOSI") (class "Default")
      (node (ref "U4") (pin "27") (pinfunction "PC1_27") (pintype "bidirectional"))
    )
    (net (code "99") (name "/SPI2_NSS") (class "Default")
      (node (ref "U4") (pin "26") (pinfunction "PC0_26") (pintype "bidirectional"))
    )
    (net (code "100") (name "/SPI4_CLK") (class "Default")
      (node (ref "U4") (pin "1") (pinfunction "PE2_1") (pintype "bidirectional"))
    )
    (net (code "101") (name "/SPI4_MISO") (class "Default")
      (node (ref "U4") (pin "67") (pinfunction "PE14_67") (pintype "bidirectional"))
    )
    (net (code "102") (name "/SPI4_MOSI") (class "Default")
      (node (ref "U4") (pin "66") (pinfunction "PE13_66") (pintype "bidirectional"))
    )
    (net (code "103") (name "/SPI4_NSS") (class "Default")
      (node (ref "U4") (pin "59") (pinfunction "PE8_59") (pintype "bidirectional"))
    )
    (net (code "104") (name "/SPK_SEL") (class "Default")
      (node (ref "U3") (pin "1") (pinfunction "~{SD}_1") (pintype "passive"))
      (node (ref "U4") (pin "44") (pinfunction "PC4_44") (pintype "bidirectional"))
    )
    (net (code "105") (name "/SUB_SW") (class "Default")
      (node (ref "U4") (pin "57") (pinfunction "PG1_57") (pintype "bidirectional"))
    )
    (net (code "106") (name "/TCK") (class "Default")
      (node (ref "P11") (pin "4") (pinfunction "TCLK_4") (pintype "passive"))
      (node (ref "U4") (pin "109") (pinfunction "PA14_109") (pintype "bidirectional"))
    )
    (net (code "107") (name "/TDI{slash}CS") (class "Default")
      (node (ref "P11") (pin "8") (pinfunction "TDI_8") (pintype "passive"))
      (node (ref "U4") (pin "110") (pinfunction "PA15_110") (pintype "bidirectional"))
    )
    (net (code "108") (name "/TDO") (class "Default")
      (node (ref "P11") (pin "6") (pinfunction "TDO_6") (pintype "passive"))
      (node (ref "U4") (pin "133") (pinfunction "PB3_133") (pintype "bidirectional"))
    )
    (net (code "109") (name "/TMS") (class "Default")
      (node (ref "P11") (pin "2") (pinfunction "TMS_2") (pintype "passive"))
      (node (ref "U4") (pin "105") (pinfunction "PA13_105") (pintype "bidirectional"))
    )
    (net (code "110") (name "/Temp_SCL") (class "Default")
      (node (ref "R1") (pin "1") (pinfunction "1_1") (pintype "passive"))
      (node (ref "U1") (pin "4") (pinfunction "SCL_4") (pintype "passive"))
      (node (ref "U2") (pin "6") (pinfunction "SCL_6") (pintype "open_collector"))
      (node (ref "U4") (pin "100") (pinfunction "PA8_100") (pintype "bidirectional"))
    )
    (net (code "111") (name "/Temp_SDA") (class "Default")
      (node (ref "R2") (pin "1") (pinfunction "1_1") (pintype "passive"))
      (node (ref "U1") (pin "5") (pinfunction "SDA_5") (pintype "passive"))
      (node (ref "U2") (pin "1") (pinfunction "SDA_1") (pintype "bidirectional"))
      (node (ref "U4") (pin "99") (pinfunction "PC9_99") (pintype "bidirectional"))
    )
    (net (code "112") (name "/U1_ECHO") (class "Default")
      (node (ref "P2") (pin "3") (pinfunction "3_3") (pintype "passive"))
      (node (ref "U4") (pin "74") (pinfunction "PB13_74") (pintype "bidirectional"))
    )
    (net (code "113") (name "/U1_TRIG") (class "Default")
      (node (ref "P2") (pin "2") (pinfunction "2_2") (pintype "passive"))
      (node (ref "U4") (pin "75") (pinfunction "PB14_75") (pintype "bidirectional"))
    )
    (net (code "114") (name "/U2_ECHO") (class "Default")
      (node (ref "P5") (pin "3") (pinfunction "3_3") (pintype "passive"))
      (node (ref "U4") (pin "73") (pinfunction "PB12_73") (pintype "bidirectional"))
    )
    (net (code "115") (name "/U2_TRIG") (class "Default")
      (node (ref "P5") (pin "2") (pinfunction "2_2") (pintype "passive"))
      (node (ref "U4") (pin "76") (pinfunction "PB15_76") (pintype "bidirectional"))
    )
    (net (code "116") (name "/U3_ECHO") (class "Default")
      (node (ref "P4") (pin "3") (pinfunction "3_3") (pintype "passive"))
      (node (ref "U4") (pin "2") (pinfunction "PE3_2") (pintype "bidirectional"))
    )
    (net (code "117") (name "/U3_TRIG") (class "Default")
      (node (ref "P4") (pin "2") (pinfunction "2_2") (pintype "passive"))
      (node (ref "U4") (pin "5") (pinfunction "PE6_5") (pintype "bidirectional"))
    )
    (net (code "118") (name "/U4_ECHO") (class "Default")
      (node (ref "P24") (pin "4") (pinfunction "4_4") (pintype "passive"))
      (node (ref "P3") (pin "3") (pinfunction "3_3") (pintype "passive"))
      (node (ref "U4") (pin "3") (pinfunction "PE4_3") (pintype "bidirectional"))
    )
    (net (code "119") (name "/U4_TRIG") (class "Default")
      (node (ref "P24") (pin "3") (pinfunction "3_3") (pintype "passive"))
      (node (ref "P3") (pin "2") (pinfunction "2_2") (pintype "passive"))
      (node (ref "U4") (pin "4") (pinfunction "PE5_4") (pintype "bidirectional"))
    )
    (net (code "120") (name "/UART_RX") (class "Default")
      (node (ref "U4") (pin "18") (pinfunction "PF6_18") (pintype "bidirectional"))
    )
    (net (code "121") (name "/UART_TX") (class "Default")
      (node (ref "U4") (pin "19") (pinfunction "PF7_19") (pintype "bidirectional"))
    )
    (net (code "122") (name "/UD+") (class "Default")
      (node (ref "C14") (pin "1") (pinfunction "1_1") (pintype "passive"))
      (node (ref "R5") (pin "1") (pinfunction "1_1") (pintype "passive"))
      (node (ref "U4") (pin "104") (pinfunction "PA12_104") (pintype "bidirectional"))
      (node (ref "U5") (pin "2") (pinfunction "2_2") (pintype "passive"))
    )
    (net (code "123") (name "/UD-") (class "Default")
      (node (ref "C15") (pin "1") (pinfunction "1_1") (pintype "passive"))
      (node (ref "R4") (pin "1") (pinfunction "1_1") (pintype "passive"))
      (node (ref "U4") (pin "103") (pinfunction "PA11_103") (pintype "bidirectional"))
      (node (ref "U5") (pin "1") (pinfunction "1_1") (pintype "passive"))
    )
    (net (code "124") (name "/USBRX") (class "Default")
      (node (ref "U4") (pin "101") (pinfunction "PA9_101") (pintype "bidirectional"))
      (node (ref "U9") (pin "4") (pinfunction "RXD_4") (pintype "input"))
    )
    (net (code "125") (name "/USBTX") (class "Default")
      (node (ref "U4") (pin "102") (pinfunction "PA10_102") (pintype "bidirectional"))
      (node (ref "U9") (pin "20") (pinfunction "TXD_20") (pintype "output"))
    )
    (net (code "126") (name "/nRST") (class "Default")
      (node (ref "C37") (pin "1") (pinfunction "1_1") (pintype "passive"))
      (node (ref "P11") (pin "10") (pinfunction "~{RESET}_10") (pintype "passive"))
      (node (ref "R12") (pin "1") (pinfunction "1_1") (pintype "passive"))
      (node (ref "S2") (pin "1") (pinfunction "1_1") (pintype "passive"))
      (node (ref "S2") (pin "2") (pinfunction "2_2") (pintype "passive"))
      (node (ref "U4") (pin "25") (pinfunction "NRST_25") (pintype "bidirectional"))
    )
    (net (code "127") (name "3.3V") (class "Default")
      (node (ref "C10") (pin "1") (pinfunction "1_1") (pintype "passive"))
      (node (ref "C20") (pin "1") (pinfunction "1_1") (pintype "passive"))
      (node (ref "C24") (pin "1") (pinfunction "1_1") (pintype "passive"))
      (node (ref "C25") (pin "1") (pinfunction "1_1") (pintype "passive"))
      (node (ref "C28") (pin "1") (pinfunction "1_1") (pintype "passive"))
      (node (ref "C29") (pin "1") (pinfunction "1_1") (pintype "passive"))
      (node (ref "C30") (pin "1") (pinfunction "1_1") (pintype "passive"))
      (node (ref "C31") (pin "1") (pinfunction "1_1") (pintype "passive"))
      (node (ref "C32") (pin "1") (pinfunction "1_1") (pintype "passive"))
      (node (ref "C33") (pin "1") (pinfunction "1_1") (pintype "passive"))
      (node (ref "C34") (pin "1") (pinfunction "1_1") (pintype "passive"))
      (node (ref "C35") (pin "1") (pinfunction "1_1") (pintype "passive"))
      (node (ref "C4") (pin "1") (pinfunction "1_1") (pintype "passive"))
      (node (ref "C9") (pin "1") (pinfunction "1_1") (pintype "passive"))
      (node (ref "L3") (pin "2") (pinfunction "2_2") (pintype "passive"))
      (node (ref "P11") (pin "1") (pinfunction "VCC_1") (pintype "passive"))
      (node (ref "P9") (pin "3") (pinfunction "3_3") (pintype "passive"))
      (node (ref "R12") (pin "2") (pinfunction "2_2") (pintype "passive"))
      (node (ref "R3") (pin "2") (pinfunction "2_2") (pintype "passive"))
      (node (ref "R6") (pin "2") (pinfunction "2_2") (pintype "passive"))
      (node (ref "R8") (pin "1") (pinfunction "1_1") (pintype "passive"))
      (node (ref "R9") (pin "1") (pinfunction "1_1") (pintype "passive"))
      (node (ref "U3") (pin "6") (pinfunction "VDD_6") (pintype "passive"))
      (node (ref "U4") (pin "108") (pinfunction "VDD_108") (pintype "power_in"))
      (node (ref "U4") (pin "121") (pinfunction "VDDSDMMC_121") (pintype "power_in"))
      (node (ref "U4") (pin "131") (pinfunction "VDD_131") (pintype "power_in"))
      (node (ref "U4") (pin "144") (pinfunction "VDD_144") (pintype "power_in"))
      (node (ref "U4") (pin "17") (pinfunction "VDD_17") (pintype "power_in"))
      (node (ref "U4") (pin "30") (pinfunction "VDD_30") (pintype "power_in"))
      (node (ref "U4") (pin "39") (pinfunction "VDD_39") (pintype "power_in"))
      (node (ref "U4") (pin "52") (pinfunction "VDD_52") (pintype "power_in"))
      (node (ref "U4") (pin "6") (pinfunction "VBAT_6") (pintype "power_in"))
      (node (ref "U4") (pin "62") (pinfunction "VDD_62") (pintype "power_in"))
      (node (ref "U4") (pin "72") (pinfunction "VDD_72") (pintype "power_in"))
      (node (ref "U4") (pin "84") (pinfunction "VDD_84") (pintype "power_in"))
      (node (ref "U4") (pin "95") (pinfunction "VDDUSB_95") (pintype "power_in"))
      (node (ref "U7") (pin "1") (pinfunction "VCC_1") (pintype "passive"))
      (node (ref "U8") (pin "22") (pinfunction "V_BCKP_22") (pintype "passive"))
      (node (ref "U8") (pin "23") (pinfunction "VCC_23") (pintype "passive"))
    )
    (net (code "128") (name "5V") (class "Default")
      (node (ref "C1") (pin "1") (pinfunction "1_1") (pintype "passive"))
      (node (ref "C5") (pin "1") (pinfunction "1_1") (pintype "passive"))
      (node (ref "C6") (pin "1") (pinfunction "1_1") (pintype "passive"))
      (node (ref "C7") (pin "1") (pinfunction "1_1") (pintype "passive"))
      (node (ref "C8") (pin "1") (pinfunction "1_1") (pintype "passive"))
      (node (ref "P2") (pin "1") (pinfunction "1_1") (pintype "passive"))
      (node (ref "P24") (pin "1") (pinfunction "1_1") (pintype "passive"))
      (node (ref "P3") (pin "1") (pinfunction "1_1") (pintype "passive"))
      (node (ref "P4") (pin "1") (pinfunction "1_1") (pintype "passive"))
      (node (ref "P5") (pin "1") (pinfunction "1_1") (pintype "passive"))
      (node (ref "P6") (pin "5") (pinfunction "5_5") (pintype "passive"))
      (node (ref "P7") (pin "2") (pinfunction "2_2") (pintype "passive"))
      (node (ref "P7") (pin "4") (pinfunction "4_4") (pintype "passive"))
      (node (ref "P8") (pin "1") (pinfunction "VMOTO_1") (pintype "passive"))
      (node (ref "P8") (pin "4") (pinfunction "VCC_4") (pintype "passive"))
      (node (ref "R1") (pin "2") (pinfunction "2_2") (pintype "passive"))
      (node (ref "R2") (pin "2") (pinfunction "2_2") (pintype "passive"))
      (node (ref "U1") (pin "1") (pinfunction "VDD_1") (pintype "passive"))
      (node (ref "U2") (pin "5") (pinfunction "VDD_5") (pintype "power_in"))
      (node (ref "U6") (pin "1") (pinfunction "VDD_1") (pintype "power_in"))
      (node (ref "U6") (pin "3") (pinfunction "EN_3") (pintype "passive"))
    )
    (net (code "129") (name "5V_U_RAW") (class "Default")
      (node (ref "C11") (pin "2") (pinfunction "2_2") (pintype "passive"))
      (node (ref "C19") (pin "1") (pinfunction "1_1") (pintype "passive"))
      (node (ref "C21") (pin "1") (pinfunction "1_1") (pintype "passive"))
      (node (ref "J1") (pin "1") (pinfunction "VUSB_1") (pintype "passive"))
      (node (ref "J2") (pin "1") (pinfunction "VUSB_1") (pintype "passive"))
      (node (ref "U9") (pin "15") (pinfunction "VCC_15") (pintype "power_in"))
    )
    (net (code "130") (name "GND") (class "Default")
      (node (ref "C1") (pin "2") (pinfunction "2_2") (pintype "passive"))
      (node (ref "C10") (pin "2") (pinfunction "2_2") (pintype "passive"))
      (node (ref "C11") (pin "1") (pinfunction "1_1") (pintype "passive"))
      (node (ref "C12") (pin "2") (pinfunction "2_2") (pintype "passive"))
      (node (ref "C13") (pin "2") (pinfunction "2_2") (pintype "passive"))
      (node (ref "C14") (pin "2") (pinfunction "2_2") (pintype "passive"))
      (node (ref "C15") (pin "2") (pinfunction "2_2") (pintype "passive"))
      (node (ref "C16") (pin "2") (pinfunction "2_2") (pintype "passive"))
      (node (ref "C17") (pin "2") (pinfunction "2_2") (pintype "passive"))
      (node (ref "C18") (pin "2") (pinfunction "2_2") (pintype "passive"))
      (node (ref "C19") (pin "2") (pinfunction "2_2") (pintype "passive"))
      (node (ref "C2") (pin "2") (pinfunction "2_2") (pintype "passive"))
      (node (ref "C20") (pin "2") (pinfunction "2_2") (pintype "passive"))
      (node (ref "C21") (pin "2") (pinfunction "2_2") (pintype "passive"))
      (node (ref "C22") (pin "2") (pinfunction "2_2") (pintype "passive"))
      (node (ref "C23") (pin "2") (pinfunction "2_2") (pintype "passive"))
      (node (ref "C24") (pin "2") (pinfunction "2_2") (pintype "passive"))
      (node (ref "C25") (pin "2") (pinfunction "2_2") (pintype "passive"))
      (node (ref "C26") (pin "2") (pinfunction "2_2") (pintype "passive"))
      (node (ref "C27") (pin "2") (pinfunction "2_2") (pintype "passive"))
      (node (ref "C28") (pin "2") (pinfunction "2_2") (pintype "passive"))
      (node (ref "C29") (pin "2") (pinfunction "2_2") (pintype "passive"))
      (node (ref "C3") (pin "2") (pinfunction "2_2") (pintype "passive"))
      (node (ref "C30") (pin "2") (pinfunction "2_2") (pintype "passive"))
      (node (ref "C31") (pin "2") (pinfunction "2_2") (pintype "passive"))
      (node (ref "C32") (pin "2") (pinfunction "2_2") (pintype "passive"))
      (node (ref "C33") (pin "2") (pinfunction "2_2") (pintype "passive"))
      (node (ref "C34") (pin "2") (pinfunction "2_2") (pintype "passive"))
      (node (ref "C35") (pin "2") (pinfunction "2_2") (pintype "passive"))
      (node (ref "C36") (pin "2") (pinfunction "2_2") (pintype "passive"))
      (node (ref "C37") (pin "2") (pinfunction "2_2") (pintype "passive"))
      (node (ref "C4") (pin "2") (pinfunction "2_2") (pintype "passive"))
      (node (ref "C5") (pin "2") (pinfunction "2_2") (pintype "passive"))
      (node (ref "C6") (pin "2") (pinfunction "2_2") (pintype "passive"))
      (node (ref "C7") (pin "2") (pinfunction "2_2") (pintype "passive"))
      (node (ref "C8") (pin "2") (pinfunction "2_2") (pintype "passive"))
      (node (ref "C9") (pin "2") (pinfunction "2_2") (pintype "passive"))
      (node (ref "J1") (pin "5") (pinfunction "GND_5") (pintype "passive"))
      (node (ref "J1") (pin "S1") (pinfunction "SHIELD_S1") (pintype "passive"))
      (node (ref "J1") (pin "S2") (pinfunction "SHIELD_S2") (pintype "passive"))
      (node (ref "J1") (pin "S3") (pinfunction "SHIELD_S3") (pintype "passive"))
      (node (ref "J1") (pin "S4") (pinfunction "SHIELD_S4") (pintype "passive"))
      (node (ref "J1") (pin "S5") (pinfunction "SHIELD_S5") (pintype "passive"))
      (node (ref "J1") (pin "S6") (pinfunction "SHIELD_S6") (pintype "passive"))
      (node (ref "J2") (pin "5") (pinfunction "GND_5") (pintype "passive"))
      (node (ref "J2") (pin "S1") (pinfunction "SHIELD_S1") (pintype "passive"))
      (node (ref "J2") (pin "S2") (pinfunction "SHIELD_S2") (pintype "passive"))
      (node (ref "J2") (pin "S3") (pinfunction "SHIELD_S3") (pintype "passive"))
      (node (ref "J2") (pin "S4") (pinfunction "SHIELD_S4") (pintype "passive"))
      (node (ref "J2") (pin "S5") (pinfunction "SHIELD_S5") (pintype "passive"))
      (node (ref "J2") (pin "S6") (pinfunction "SHIELD_S6") (pintype "passive"))
      (node (ref "J3") (pin "1") (pinfunction "GND_1") (pintype "passive"))
      (node (ref "J3") (pin "2") (pinfunction "GND_2") (pintype "passive"))
      (node (ref "P10") (pin "3") (pinfunction "3_3") (pintype "passive"))
      (node (ref "P10") (pin "4") (pinfunction "4_4") (pintype "passive"))
      (node (ref "P11") (pin "3") (pinfunction "GND_3") (pintype "passive"))
      (node (ref "P11") (pin "5") (pinfunction "GND_5") (pintype "passive"))
      (node (ref "P11") (pin "9") (pinfunction "GND_9") (pintype "passive"))
      (node (ref "P2") (pin "4") (pinfunction "4_4") (pintype "passive"))
      (node (ref "P24") (pin "2") (pinfunction "2_2") (pintype "passive"))
      (node (ref "P3") (pin "4") (pinfunction "4_4") (pintype "passive"))
      (node (ref "P4") (pin "4") (pinfunction "4_4") (pintype "passive"))
      (node (ref "P5") (pin "4") (pinfunction "4_4") (pintype "passive"))
      (node (ref "P6") (pin "2") (pinfunction "2_2") (pintype "passive"))
      (node (ref "P7") (pin "14") (pinfunction "14_14") (pintype "passive"))
      (node (ref "P7") (pin "20") (pinfunction "20_20") (pintype "passive"))
      (node (ref "P7") (pin "25") (pinfunction "25_25") (pintype "passive"))
      (node (ref "P7") (pin "30") (pinfunction "30_30") (pintype "passive"))
      (node (ref "P7") (pin "34") (pinfunction "34_34") (pintype "passive"))
      (node (ref "P7") (pin "39") (pinfunction "39_39") (pintype "passive"))
      (node (ref "P7") (pin "6") (pinfunction "6_6") (pintype "passive"))
      (node (ref "P7") (pin "9") (pinfunction "9_9") (pintype "passive"))
      (node (ref "P8") (pin "3") (pinfunction "GND_3") (pintype "passive"))
      (node (ref "P8") (pin "7") (pinfunction "GND_7") (pintype "passive"))
      (node (ref "P9") (pin "2") (pinfunction "2_2") (pintype "passive"))
      (node (ref "R7") (pin "2") (pinfunction "2_2") (pintype "passive"))
      (node (ref "S1") (pin "3") (pinfunction "3_3") (pintype "passive"))
      (node (ref "S1") (pin "4") (pinfunction "4_4") (pintype "passive"))
      (node (ref "S2") (pin "3") (pinfunction "3_3") (pintype "passive"))
      (node (ref "S2") (pin "4") (pinfunction "4_4") (pintype "passive"))
      (node (ref "U1") (pin "2") (pinfunction "VSS_2") (pintype "passive"))
      (node (ref "U10") (pin "3") (pinfunction "3_3") (pintype "passive"))
      (node (ref "U2") (pin "2") (pinfunction "GND_2") (pintype "power_in"))
      (node (ref "U2") (pin "7") (pinfunction "PAD_7") (pintype "power_in"))
      (node (ref "U3") (pin "4") (pinfunction "IN-_4") (pintype "passive"))
      (node (ref "U3") (pin "7") (pinfunction "GND_7") (pintype "passive"))
      (node (ref "U4") (pin "107") (pinfunction "VSS_107") (pintype "power_in"))
      (node (ref "U4") (pin "120") (pinfunction "VSS_120") (pintype "power_in"))
      (node (ref "U4") (pin "130") (pinfunction "VSS_130") (pintype "power_in"))
      (node (ref "U4") (pin "143") (pinfunction "PDR_ON_143") (pintype "passive"))
      (node (ref "U4") (pin "16") (pinfunction "VSS_16") (pintype "power_in"))
      (node (ref "U4") (pin "31") (pinfunction "VSSA_31") (pintype "power_in"))
      (node (ref "U4") (pin "38") (pinfunction "VSS_38") (pintype "power_in"))
      (node (ref "U4") (pin "51") (pinfunction "VSS_51") (pintype "power_in"))
      (node (ref "U4") (pin "61") (pinfunction "VSS_61") (pintype "power_in"))
      (node (ref "U4") (pin "83") (pinfunction "VSS_83") (pintype "power_in"))
      (node (ref "U4") (pin "94") (pinfunction "VSS_94") (pintype "power_in"))
      (node (ref "U5") (pin "3") (pinfunction "3_3") (pintype "passive"))
      (node (ref "U6") (pin "2") (pinfunction "GND_2") (pintype "passive"))
      (node (ref "U7") (pin "2") (pinfunction "GND_2") (pintype "passive"))
      (node (ref "U8") (pin "10") (pinfunction "GND_10") (pintype "passive"))
      (node (ref "U8") (pin "12") (pinfunction "GND_12") (pintype "passive"))
      (node (ref "U8") (pin "13") (pinfunction "GND_13") (pintype "passive"))
      (node (ref "U8") (pin "24") (pinfunction "GND_24") (pintype "passive"))
      (node (ref "U9") (pin "16") (pinfunction "GND_16") (pintype "power_in"))
      (node (ref "U9") (pin "6") (pinfunction "GND_6") (pintype "power_in"))
    )
    (net (code "131") (name "Net-(C2-Pad1)") (class "Default")
      (node (ref "C2") (pin "1") (pinfunction "1_1") (pintype "passive"))
      (node (ref "L1") (pin "2") (pinfunction "2_2") (pintype "passive"))
      (node (ref "P1") (pin "1") (pinfunction "1_1") (pintype "passive"))
    )
    (net (code "132") (name "Net-(C3-Pad1)") (class "Default")
      (node (ref "C3") (pin "1") (pinfunction "1_1") (pintype "passive"))
      (node (ref "L2") (pin "2") (pinfunction "2_2") (pintype "passive"))
      (node (ref "P1") (pin "2") (pinfunction "2_2") (pintype "passive"))
    )
    (net (code "133") (name "Net-(J1-D+)") (class "Default")
      (node (ref "J1") (pin "3") (pinfunction "D+_3") (pintype "passive"))
      (node (ref "R5") (pin "2") (pinfunction "2_2") (pintype "passive"))
    )
    (net (code "134") (name "Net-(J1-D-)") (class "Default")
      (node (ref "J1") (pin "2") (pinfunction "D-_2") (pintype "passive"))
      (node (ref "R4") (pin "2") (pinfunction "2_2") (pintype "passive"))
    )
    (net (code "135") (name "Net-(J3-SIG)") (class "Default")
      (node (ref "J3") (pin "3") (pinfunction "SIG_3") (pintype "passive"))
      (node (ref "U8") (pin "11") (pinfunction "RF_IN_11") (pintype "passive"))
    )
    (net (code "136") (name "Net-(U3-VO+)") (class "Default")
      (node (ref "L2") (pin "1") (pinfunction "1_1") (pintype "passive"))
      (node (ref "U3") (pin "5") (pinfunction "VO+_5") (pintype "passive"))
    )
    (net (code "137") (name "Net-(U3-VO-)") (class "Default")
      (node (ref "L1") (pin "1") (pinfunction "1_1") (pintype "passive"))
      (node (ref "U3") (pin "8") (pinfunction "VO-_8") (pintype "passive"))
    )
    (net (code "138") (name "Net-(U4B-BOOT0)") (class "Default")
      (node (ref "R6") (pin "1") (pinfunction "1_1") (pintype "passive"))
      (node (ref "R7") (pin "1") (pinfunction "1_1") (pintype "passive"))
      (node (ref "U4") (pin "138") (pinfunction "BOOT0_138") (pintype "input"))
    )
    (net (code "139") (name "Net-(U4B-PH0)") (class "Default")
      (node (ref "C13") (pin "1") (pinfunction "1_1") (pintype "passive"))
      (node (ref "U4") (pin "23") (pinfunction "PH0_23") (pintype "bidirectional"))
      (node (ref "XTAL1") (pin "2") (pinfunction "OSC2_2") (pintype "passive"))
    )
    (net (code "140") (name "Net-(U4B-PH1)") (class "Default")
      (node (ref "C16") (pin "1") (pinfunction "1_1") (pintype "passive"))
      (node (ref "U4") (pin "24") (pinfunction "PH1_24") (pintype "bidirectional"))
      (node (ref "XTAL1") (pin "1") (pinfunction "OSC1_1") (pintype "passive"))
    )
    (net (code "141") (name "Net-(U4C-VCAP_1)") (class "Default")
      (node (ref "C23") (pin "1") (pinfunction "1_1") (pintype "passive"))
      (node (ref "U4") (pin "71") (pinfunction "VCAP_1_71") (pintype "power_in"))
    )
    (net (code "142") (name "Net-(U4C-VCAP_2)") (class "Default")
      (node (ref "C22") (pin "1") (pinfunction "1_1") (pintype "passive"))
      (node (ref "U4") (pin "106") (pinfunction "VCAP_2_106") (pintype "power_in"))
    )
    (net (code "143") (name "Net-(U4C-VDDA)") (class "Default")
      (node (ref "L3") (pin "1") (pinfunction "1_1") (pintype "passive"))
      (node (ref "U4") (pin "32") (pinfunction "VREF+_32") (pintype "power_in"))
      (node (ref "U4") (pin "33") (pinfunction "VDDA_33") (pintype "power_in"))
    )
    (net (code "144") (name "Net-(U6-OUT)") (class "Default")
      (node (ref "C17") (pin "1") (pinfunction "1_1") (pintype "passive"))
      (node (ref "C18") (pin "1") (pinfunction "1_1") (pintype "passive"))
      (node (ref "P10") (pin "1") (pinfunction "1_1") (pintype "passive"))
      (node (ref "U6") (pin "5") (pinfunction "OUT_5") (pintype "output"))
    )
    (net (code "145") (name "Net-(U9-3V3OUT)") (class "Default")
      (node (ref "C36") (pin "1") (pinfunction "1_1") (pintype "passive"))
      (node (ref "U9") (pin "13") (pinfunction "3V3OUT_13") (pintype "power_in"))
      (node (ref "U9") (pin "14") (pinfunction "RESET#_14") (pintype "input"))
      (node (ref "U9") (pin "3") (pinfunction "VCCIO_3") (pintype "power_in"))
    )
    (net (code "146") (name "Net-(U9-USBDM)") (class "Default")
      (node (ref "R10") (pin "2") (pinfunction "2_2") (pintype "passive"))
      (node (ref "U9") (pin "12") (pinfunction "USBDM_12") (pintype "input"))
    )
    (net (code "147") (name "Net-(U9-USBDP)") (class "Default")
      (node (ref "R11") (pin "2") (pinfunction "2_2") (pintype "passive"))
      (node (ref "U9") (pin "11") (pinfunction "USBDP_11") (pintype "input"))
    )
    (net (code "148") (name "unconnected-(J1-ID-Pad4)") (class "Default")
      (node (ref "J1") (pin "4") (pinfunction "ID_4") (pintype "passive"))
    )
    (net (code "149") (name "unconnected-(J2-ID-Pad4)") (class "Default")
      (node (ref "J2") (pin "4") (pinfunction "ID_4") (pintype "passive"))
    )
    (net (code "150") (name "unconnected-(P7-Pad1)") (class "Default")
      (node (ref "P7") (pin "1") (pinfunction "1_1") (pintype "passive"))
    )
    (net (code "151") (name "unconnected-(P7-Pad7)") (class "Default")
      (node (ref "P7") (pin "7") (pinfunction "7_7") (pintype "passive"))
    )
    (net (code "152") (name "unconnected-(P7-Pad11)") (class "Default")
      (node (ref "P7") (pin "11") (pinfunction "11_11") (pintype "passive"))
    )
    (net (code "153") (name "unconnected-(P7-Pad12)") (class "Default")
      (node (ref "P7") (pin "12") (pinfunction "12_12") (pintype "passive"))
    )
    (net (code "154") (name "unconnected-(P7-Pad13)") (class "Default")
      (node (ref "P7") (pin "13") (pinfunction "13_13") (pintype "passive"))
    )
    (net (code "155") (name "unconnected-(P7-Pad15)") (class "Default")
      (node (ref "P7") (pin "15") (pinfunction "15_15") (pintype "passive"))
    )
    (net (code "156") (name "unconnected-(P7-Pad16)") (class "Default")
      (node (ref "P7") (pin "16") (pinfunction "16_16") (pintype "passive"))
    )
    (net (code "157") (name "unconnected-(P7-Pad17)") (class "Default")
      (node (ref "P7") (pin "17") (pinfunction "17_17") (pintype "passive"))
    )
    (net (code "158") (name "unconnected-(P7-Pad18)") (class "Default")
      (node (ref "P7") (pin "18") (pinfunction "18_18") (pintype "passive"))
    )
    (net (code "159") (name "unconnected-(P7-Pad24)") (class "Default")
      (node (ref "P7") (pin "24") (pinfunction "24_24") (pintype "passive"))
    )
    (net (code "160") (name "unconnected-(P7-Pad26)") (class "Default")
      (node (ref "P7") (pin "26") (pinfunction "26_26") (pintype "passive"))
    )
    (net (code "161") (name "unconnected-(P7-Pad27)") (class "Default")
      (node (ref "P7") (pin "27") (pinfunction "27_27") (pintype "passive"))
    )
    (net (code "162") (name "unconnected-(P7-Pad28)") (class "Default")
      (node (ref "P7") (pin "28") (pinfunction "28_28") (pintype "passive"))
    )
    (net (code "163") (name "unconnected-(P7-Pad29)") (class "Default")
      (node (ref "P7") (pin "29") (pinfunction "29_29") (pintype "passive"))
    )
    (net (code "164") (name "unconnected-(P7-Pad31)") (class "Default")
      (node (ref "P7") (pin "31") (pinfunction "31_31") (pintype "passive"))
    )
    (net (code "165") (name "unconnected-(P7-Pad32)") (class "Default")
      (node (ref "P7") (pin "32") (pinfunction "32_32") (pintype "passive"))
    )
    (net (code "166") (name "unconnected-(P7-Pad33)") (class "Default")
      (node (ref "P7") (pin "33") (pinfunction "33_33") (pintype "passive"))
    )
    (net (code "167") (name "unconnected-(P7-Pad35)") (class "Default")
      (node (ref "P7") (pin "35") (pinfunction "35_35") (pintype "passive"))
    )
    (net (code "168") (name "unconnected-(P7-Pad36)") (class "Default")
      (node (ref "P7") (pin "36") (pinfunction "36_36") (pintype "passive"))
    )
    (net (code "169") (name "unconnected-(P7-Pad37)") (class "Default")
      (node (ref "P7") (pin "37") (pinfunction "37_37") (pintype "passive"))
    )
    (net (code "170") (name "unconnected-(P10-Pad2)") (class "Default")
      (node (ref "P10") (pin "2") (pinfunction "2_2") (pintype "passive"))
    )
    (net (code "171") (name "unconnected-(P10-Pad5)") (class "Default")
      (node (ref "P10") (pin "5") (pinfunction "5_5") (pintype "passive"))
    )
    (net (code "172") (name "unconnected-(P10-Pad6)") (class "Default")
      (node (ref "P10") (pin "6") (pinfunction "6_6") (pintype "passive"))
    )
    (net (code "173") (name "unconnected-(P10-Pad7)") (class "Default")
      (node (ref "P10") (pin "7") (pinfunction "7_7") (pintype "passive"))
    )
    (net (code "174") (name "unconnected-(P10-Pad8)") (class "Default")
      (node (ref "P10") (pin "8") (pinfunction "8_8") (pintype "passive"))
    )
    (net (code "175") (name "unconnected-(P10-Pad9)") (class "Default")
      (node (ref "P10") (pin "9") (pinfunction "9_9") (pintype "passive"))
    )
    (net (code "176") (name "unconnected-(P10-Pad11)") (class "Default")
      (node (ref "P10") (pin "11") (pinfunction "11_11") (pintype "passive"))
    )
    (net (code "177") (name "unconnected-(P10-Pad13)") (class "Default")
      (node (ref "P10") (pin "13") (pinfunction "13_13") (pintype "passive"))
    )
    (net (code "178") (name "unconnected-(P10-Pad15)") (class "Default")
      (node (ref "P10") (pin "15") (pinfunction "15_15") (pintype "passive"))
    )
    (net (code "179") (name "unconnected-(P10-Pad17)") (class "Default")
      (node (ref "P10") (pin "17") (pinfunction "17_17") (pintype "passive"))
    )
    (net (code "180") (name "unconnected-(P10-Pad19)") (class "Default")
      (node (ref "P10") (pin "19") (pinfunction "19_19") (pintype "passive"))
    )
    (net (code "181") (name "unconnected-(P10-Pad20)") (class "Default")
      (node (ref "P10") (pin "20") (pinfunction "20_20") (pintype "passive"))
    )
    (net (code "182") (name "unconnected-(P10-Pad21)") (class "Default")
      (node (ref "P10") (pin "21") (pinfunction "21_21") (pintype "passive"))
    )
    (net (code "183") (name "unconnected-(P10-Pad23)") (class "Default")
      (node (ref "P10") (pin "23") (pinfunction "23_23") (pintype "passive"))
    )
    (net (code "184") (name "unconnected-(P10-Pad24)") (class "Default")
      (node (ref "P10") (pin "24") (pinfunction "24_24") (pintype "passive"))
    )
    (net (code "185") (name "unconnected-(P10-Pad25)") (class "Default")
      (node (ref "P10") (pin "25") (pinfunction "25_25") (pintype "passive"))
    )
    (net (code "186") (name "unconnected-(P10-Pad26)") (class "Default")
      (node (ref "P10") (pin "26") (pinfunction "26_26") (pintype "passive"))
    )
    (net (code "187") (name "unconnected-(P10-Pad27)") (class "Default")
      (node (ref "P10") (pin "27") (pinfunction "27_27") (pintype "passive"))
    )
    (net (code "188") (name "unconnected-(P10-Pad29)") (class "Default")
      (node (ref "P10") (pin "29") (pinfunction "29_29") (pintype "passive"))
    )
    (net (code "189") (name "unconnected-(P10-Pad30)") (class "Default")
      (node (ref "P10") (pin "30") (pinfunction "30_30") (pintype "passive"))
    )
    (net (code "190") (name "unconnected-(P11-RTCK-Pad7)") (class "Default")
      (node (ref "P11") (pin "7") (pinfunction "RTCK_7") (pintype "passive"))
    )
    (net (code "191") (name "unconnected-(P24-Pad5)") (class "Default")
      (node (ref "P24") (pin "5") (pinfunction "5_5") (pintype "passive"))
    )
    (net (code "192") (name "unconnected-(PH1-Hole-Pad1)") (class "Default")
      (node (ref "PH1") (pin "1") (pinfunction "Hole_1") (pintype "passive"))
    )
    (net (code "193") (name "unconnected-(PH2-Hole-Pad1)") (class "Default")
      (node (ref "PH2") (pin "1") (pinfunction "Hole_1") (pintype "passive"))
    )
    (net (code "194") (name "unconnected-(PH3-Hole-Pad1)") (class "Default")
      (node (ref "PH3") (pin "1") (pinfunction "Hole_1") (pintype "passive"))
    )
    (net (code "195") (name "unconnected-(PH4-Hole-Pad1)") (class "Default")
      (node (ref "PH4") (pin "1") (pinfunction "Hole_1") (pintype "passive"))
    )
    (net (code "196") (name "unconnected-(PH5-Hole-Pad1)") (class "Default")
      (node (ref "PH5") (pin "1") (pinfunction "Hole_1") (pintype "passive"))
    )
    (net (code "197") (name "unconnected-(PH6-Hole-Pad1)") (class "Default")
      (node (ref "PH6") (pin "1") (pinfunction "Hole_1") (pintype "passive"))
    )
    (net (code "198") (name "unconnected-(PH7-Hole-Pad1)") (class "Default")
      (node (ref "PH7") (pin "1") (pinfunction "Hole_1") (pintype "passive"))
    )
    (net (code "199") (name "unconnected-(PH8-Hole-Pad1)") (class "Default")
      (node (ref "PH8") (pin "1") (pinfunction "Hole_1") (pintype "passive"))
    )
    (net (code "200") (name "unconnected-(PH9-Hole-Pad1)") (class "Default")
      (node (ref "PH9") (pin "1") (pinfunction "Hole_1") (pintype "passive"))
    )
    (net (code "201") (name "unconnected-(U2-NC-Pad3)") (class "Default")
      (node (ref "U2") (pin "3") (pinfunction "NC_3") (pintype "passive"))
    )
    (net (code "202") (name "unconnected-(U2-NC-Pad4)") (class "Default")
      (node (ref "U2") (pin "4") (pinfunction "NC_4") (pintype "passive"))
    )
    (net (code "203") (name "unconnected-(U3-NC-Pad2)") (class "Default")
      (node (ref "U3") (pin "2") (pinfunction "NC_2") (pintype "passive"))
    )
    (net (code "204") (name "unconnected-(U4B-PG15-Pad132)") (class "Default")
      (node (ref "U4") (pin "132") (pinfunction "PG15_132") (pintype "bidirectional"))
    )
    (net (code "205") (name "unconnected-(U6-NC-Pad4)") (class "Default")
      (node (ref "U6") (pin "4") (pinfunction "NC_4") (pintype "passive"))
    )
    (net (code "206") (name "unconnected-(U7-AD0-Pad7)") (class "Default")
      (node (ref "U7") (pin "7") (pinfunction "AD0_7") (pintype "passive"))
    )
    (net (code "207") (name "unconnected-(U7-ECL-Pad6)") (class "Default")
      (node (ref "U7") (pin "6") (pinfunction "ECL_6") (pintype "passive"))
    )
    (net (code "208") (name "unconnected-(U7-EDA-Pad5)") (class "Default")
      (node (ref "U7") (pin "5") (pinfunction "EDA_5") (pintype "passive"))
    )
    (net (code "209") (name "unconnected-(U7-FYNC-Pad10)") (class "Default")
      (node (ref "U7") (pin "10") (pinfunction "FYNC_10") (pintype "passive"))
    )
    (net (code "210") (name "unconnected-(U7-NCS-Pad9)") (class "Default")
      (node (ref "U7") (pin "9") (pinfunction "NCS_9") (pintype "passive"))
    )
    (net (code "211") (name "unconnected-(U8-BOOT_SEL-Pad1)") (class "Default")
      (node (ref "U8") (pin "1") (pinfunction "BOOT_SEL_1") (pintype "passive"))
    )
    (net (code "212") (name "unconnected-(U8-NC-Pad2)") (class "Default")
      (node (ref "U8") (pin "2") (pinfunction "NC_2") (pintype "passive"))
    )
    (net (code "213") (name "unconnected-(U8-NC-Pad4)") (class "Default")
      (node (ref "U8") (pin "4") (pinfunction "NC_4") (pintype "passive"))
    )
    (net (code "214") (name "unconnected-(U8-NC-Pad5)") (class "Default")
      (node (ref "U8") (pin "5") (pinfunction "NC_5") (pintype "passive"))
    )
    (net (code "215") (name "unconnected-(U8-NC-Pad6)") (class "Default")
      (node (ref "U8") (pin "6") (pinfunction "NC_6") (pintype "passive"))
    )
    (net (code "216") (name "unconnected-(U8-NC-Pad7)") (class "Default")
      (node (ref "U8") (pin "7") (pinfunction "NC_7") (pintype "passive"))
    )
    (net (code "217") (name "unconnected-(U8-NC-Pad9)") (class "Default")
      (node (ref "U8") (pin "9") (pinfunction "NC_9") (pintype "passive"))
    )
    (net (code "218") (name "unconnected-(U8-NC-Pad14)") (class "Default")
      (node (ref "U8") (pin "14") (pinfunction "NC_14") (pintype "passive"))
    )
    (net (code "219") (name "unconnected-(U8-NC-Pad15)") (class "Default")
      (node (ref "U8") (pin "15") (pinfunction "NC_15") (pintype "passive"))
    )
    (net (code "220") (name "unconnected-(U8-NC-Pad16)") (class "Default")
      (node (ref "U8") (pin "16") (pinfunction "NC_16") (pintype "passive"))
    )
    (net (code "221") (name "unconnected-(U8-NC-Pad17)") (class "Default")
      (node (ref "U8") (pin "17") (pinfunction "NC_17") (pintype "passive"))
    )
    (net (code "222") (name "unconnected-(U8-RSTN-Pad8)") (class "Default")
      (node (ref "U8") (pin "8") (pinfunction "RSTN_8") (pintype "passive"))
    )
    (net (code "223") (name "unconnected-(U8-SCL-Pad19)") (class "Default")
      (node (ref "U8") (pin "19") (pinfunction "SCL_19") (pintype "passive"))
    )
    (net (code "224") (name "unconnected-(U8-SDA-Pad18)") (class "Default")
      (node (ref "U8") (pin "18") (pinfunction "SDA_18") (pintype "passive"))
    )
    (net (code "225") (name "unconnected-(U9-CBUS0-Pad18)") (class "Default")
      (node (ref "U9") (pin "18") (pinfunction "CBUS0_18") (pintype "bidirectional+no_connect"))
    )
    (net (code "226") (name "unconnected-(U9-CBUS1-Pad17)") (class "Default")
      (node (ref "U9") (pin "17") (pinfunction "CBUS1_17") (pintype "bidirectional+no_connect"))
    )
    (net (code "227") (name "unconnected-(U9-CBUS2-Pad10)") (class "Default")
      (node (ref "U9") (pin "10") (pinfunction "CBUS2_10") (pintype "bidirectional+no_connect"))
    )
    (net (code "228") (name "unconnected-(U9-CBUS3-Pad19)") (class "Default")
      (node (ref "U9") (pin "19") (pinfunction "CBUS3_19") (pintype "bidirectional+no_connect"))
    )
    (net (code "229") (name "unconnected-(U9-CTS#-Pad9)") (class "Default")
      (node (ref "U9") (pin "9") (pinfunction "CTS#_9") (pintype "input+no_connect"))
    )
    (net (code "230") (name "unconnected-(U9-DCD#-Pad8)") (class "Default")
      (node (ref "U9") (pin "8") (pinfunction "DCD#_8") (pintype "input+no_connect"))
    )
    (net (code "231") (name "unconnected-(U9-DSR#-Pad7)") (class "Default")
      (node (ref "U9") (pin "7") (pinfunction "DSR#_7") (pintype "input+no_connect"))
    )
    (net (code "232") (name "unconnected-(U9-DTR#-Pad1)") (class "Default")
      (node (ref "U9") (pin "1") (pinfunction "DTR#_1") (pintype "output"))
    )
    (net (code "233") (name "unconnected-(U9-RI#-Pad5)") (class "Default")
      (node (ref "U9") (pin "5") (pinfunction "RI#_5") (pintype "input+no_connect"))
    )
    (net (code "234") (name "unconnected-(U9-RTS#-Pad2)") (class "Default")
      (node (ref "U9") (pin "2") (pinfunction "RTS#_2") (pintype "output"))
    )
  )
)
